# Sheet1.net
KiCad netlist of a schematic drawn in Altium Designer
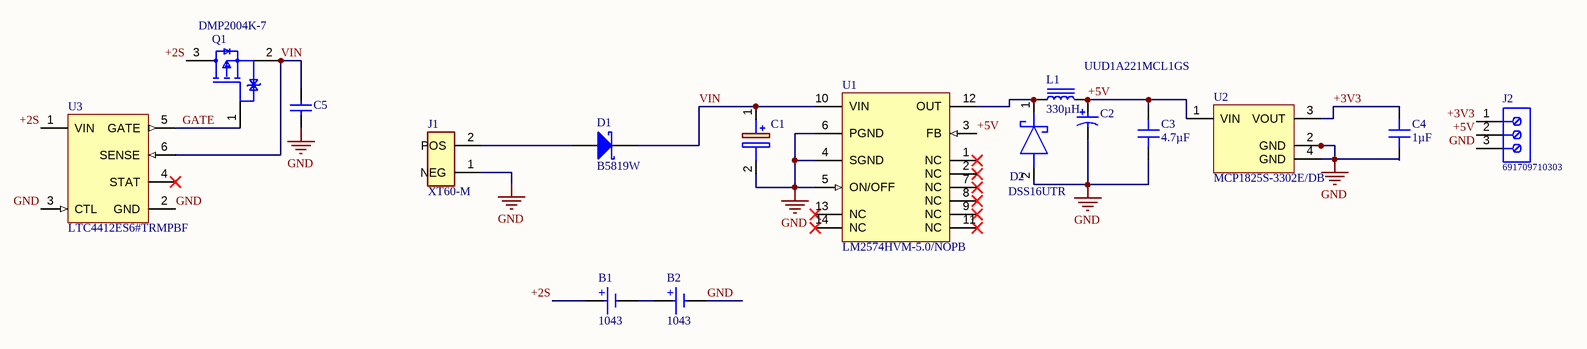
[diagram p0: Sheet1.SchDoc]

(export (version "E")
  (design (tool "Eeschema 10.0.6"))
  (components
    (comp (ref "B1")
      (value "1043")
      (footprint "KEYSTONE 1043")
      (description "BATTERY HOLDER 18650 PC PIN")
      (fields (field (name "MANUFACTURER") "Keystone Electronics"))
      (libsource (lib "Celestial Altium Library - altium_library") (part "Keystone 1043"))
    )
    (comp (ref "B2")
      (value "1043")
      (footprint "KEYSTONE 1043")
      (description "BATTERY HOLDER 18650 PC PIN")
      (fields (field (name "MANUFACTURER") "Keystone Electronics"))
      (libsource (lib "Celestial Altium Library - altium_library") (part "Keystone 1043"))
    )
    (comp (ref "C1")
      (value "EMVH500ADA220MF80G")
      (footprint "SamacSys:CAPAE660X800N")
      (description "Capacitor Polarised")
      (fields (field (name "MOUSER PART NUMBER") "661-MVH50V220M"))
      (libsource (lib "*") (part "EMVH500ADA220MF80G"))
    )
    (comp (ref "C2")
      (value "UUD1A221MCL1GS")
      (footprint "NIC-CAPA2-6.3X7.7_V")
      (fields (field (name "MANUFACTURER") "Nichicon"))
      (libsource (lib "Altium Content Vault") (part "NIC-CAP-P-2"))
    )
    (comp (ref "C3")
      (value "4.7µF")
      (footprint "CAP 1206_3216 - 1.8MM")
      (description "CAP CER 4.7UF 25V X5R 1206")
      (fields
        (field (name "PART NUMBER") "CM316X5R475K25AT")
        (field (name "MANUFACTURER") "Kyocera International Inc. Electronic Components")
      )
      (libsource (lib "Celestial Altium Library - altium_library") (part "Capacitor"))
    )
    (comp (ref "C4")
      (value "1µF")
      (footprint "CAP 1206_3216 - 1.8MM")
      (description "CAP CER 4.7UF 25V X5R 1206")
      (fields
        (field (name "PART NUMBER") "CM316X5R475K25AT")
        (field (name "MANUFACTURER") "Kyocera International Inc. Electronic Components")
      )
      (libsource (lib "Celestial Altium Library - altium_library") (part "Capacitor"))
    )
    (comp (ref "C5")
      (value "C1206C105K5RACTU")
      (footprint "CAPC3216X110X50LL20T25")
      (description "Chip Capacitor, 1 uF, +/- 10%, 50 V, -55 to 125 degC, 1206 (3216 Metric), RoHS, Tape and Reel")
      (fields (field (name "MANUFACTURER") "Kemet") (field (name "TOLERANCE") "10%"))
      (libsource (lib "Altium Content Vault") (part "CAP-NP-2"))
    )
    (comp (ref "D1")
      (value "B5819W")
      (footprint "MCC-SOD123_V")
      (description "Schottky Barrier Rectifier, 40 V, 1 A, -65 to 125 degC, 2-Pin SOD123, RoHS, Tape and Reel")
      (fields (field (name "MANUFACTURER") "Micro Commercial Components"))
      (libsource (lib "Mathewos Samson KSU") (part "DSKY-AK-2"))
    )
    (comp (ref "D2")
      (value "DSS16UTR")
      (footprint "SamacSys:SODFL3618X110N")
      (description "Schottky Diode")
      (libsource (lib "*") (part "DSS16UTR"))
    )
    (comp (ref "J1")
      (value "XT60-M")
      (footprint "AMASS_XT60-M")
      (description "Plug; DC supply; XT60; male; PIN: 2; for cable; soldered; 30A; 500V")
      (fields (field (name "MF") "AMASS"))
      (libsource (lib "XT60-M") (part "XT60-M"))
    )
    (comp (ref "J2")
      (value "691709710303")
      (footprint "691709710303")
      (description "Serie 7097 - 5.00 mm Horizontal Entry SMT with Pressure Clamp WR-TBL, 3 pin")
      (fields (field (name "MANUFACTURER") "Wurth Elektronik") (field (name "PUBLISHER") "WurthElektronik"))
      (libsource (lib "Altium Content Vault") (part "WE-CN-1P-F-TB3"))
    )
    (comp (ref "L1")
      (value "330µH")
      (footprint "BOURNS SRR1280")
      (description "FIXED IND 330UH 1.1A 600MOHM SMD")
      (fields (field (name "PART NUMBER") "SRR1280-331K") (field (name "MANUFACTURER") "Bourns Inc."))
      (libsource (lib "Celestial Altium Library - altium_library") (part "Inductor"))
    )
    (comp (ref "Q1")
      (value "DMP2004K-7")
      (footprint "FP-SOT23-MFG")
      (description "MOSFET P-CH 20V 600MA SOT23-3")
      (fields
        (field (name "OCTOPART") "https://octopart.com/dmp2004k-7-diodes+inc.-7151877")
        (field (name "MANUFACTURER") "Diodes Inc.")
      )
      (libsource (lib "Altium Content Vault") (part "0909edbb8d389a8e80b8543cd1a9d7a"))
    )
    (comp (ref "U1")
      (value "LM2574HVM-5.0/NOPB")
      (footprint "NPA0014B_L")
      (description "SIMPLE SWITCHER® 0.5A Step-Down Voltage Regulator, 14-pin Wide SOIC, Pb-Free")
      (fields (field (name "MANUFACTURER") "Texas Instruments"))
      (libsource (lib "Altium Content Vault") (part "PM-REG-LM2574HVM-12"))
    )
    (comp (ref "U2")
      (value "MCP1825S-3302E/DB")
      (footprint "SOT-223-DB3_N")
      (description "500 mA, Low Voltage, Low Quiescent Current LDO Regulator, 3-Pin SOT-223, Extended Temperature")
      (libsource (lib "Altium Content Vault") (part "PM-LINEREG-MCP1825-IL4"))
    )
    (comp (ref "U3")
      (value "LTC4412ES6#TRMPBF")
      (footprint "LT-S6-6-TSOT-23_N")
      (fields (field (name "MANUFACTURER") "Linear Technology"))
      (libsource (lib "Altium Content Vault") (part "LT-LTC4412_HV-S6-6"))
    )
  )
  (nets
    (net (code "1") (name "/+2S") (class "Default")
      (node (ref "B1") (pin "1") (pinfunction "+_1") (pintype "passive"))
      (node (ref "Q1") (pin "3") (pinfunction "D_3") (pintype "passive"))
      (node (ref "U3") (pin "1") (pinfunction "VIN_1") (pintype "power_in"))
    )
    (net (code "2") (name "/+3V3") (class "Default")
      (node (ref "C4") (pin "2") (pinfunction "2_2") (pintype "passive"))
      (node (ref "J2") (pin "1") (pinfunction "1_1") (pintype "passive"))
      (node (ref "U2") (pin "3") (pinfunction "VOUT_3") (pintype "power_in"))
    )
    (net (code "3") (name "/+5V") (class "Default")
      (node (ref "C2") (pin "1") (pinfunction "1_1") (pintype "passive"))
      (node (ref "C3") (pin "2") (pinfunction "2_2") (pintype "passive"))
      (node (ref "J2") (pin "2") (pinfunction "2_2") (pintype "passive"))
      (node (ref "L1") (pin "2") (pinfunction "2_2") (pintype "passive"))
      (node (ref "U1") (pin "3") (pinfunction "FB_3") (pintype "input"))
      (node (ref "U2") (pin "1") (pinfunction "VIN_1") (pintype "power_in"))
    )
    (net (code "4") (name "/GATE") (class "Default")
      (node (ref "Q1") (pin "1") (pinfunction "G_1") (pintype "passive"))
      (node (ref "U3") (pin "5") (pinfunction "GATE_5") (pintype "output"))
    )
    (net (code "5") (name "/VIN") (class "Default")
      (node (ref "C1") (pin "1") (pinfunction "+_1") (pintype "passive"))
      (node (ref "C5") (pin "2") (pinfunction "2_2") (pintype "passive"))
      (node (ref "D1") (pin "2") (pinfunction "K_2") (pintype "passive"))
      (node (ref "Q1") (pin "2") (pinfunction "S_2") (pintype "passive"))
      (node (ref "U1") (pin "10") (pinfunction "VIN_10") (pintype "power_in"))
      (node (ref "U3") (pin "6") (pinfunction "SENSE_6") (pintype "input"))
    )
    (net (code "6") (name "GND") (class "Default")
      (node (ref "B2") (pin "2") (pinfunction "-_2") (pintype "passive"))
      (node (ref "C1") (pin "2") (pinfunction "-_2") (pintype "passive"))
      (node (ref "C2") (pin "2") (pinfunction "2_2") (pintype "passive"))
      (node (ref "C3") (pin "1") (pinfunction "1_1") (pintype "passive"))
      (node (ref "C4") (pin "1") (pinfunction "1_1") (pintype "passive"))
      (node (ref "C5") (pin "1") (pinfunction "1_1") (pintype "passive"))
      (node (ref "D2") (pin "2") (pinfunction "A_2") (pintype "passive"))
      (node (ref "J1") (pin "1") (pinfunction "NEG_1") (pintype "passive"))
      (node (ref "J2") (pin "3") (pinfunction "3_3") (pintype "passive"))
      (node (ref "U1") (pin "4") (pinfunction "SGND_4") (pintype "power_in"))
      (node (ref "U1") (pin "5") (pinfunction "ON/OFF_5") (pintype "input"))
      (node (ref "U1") (pin "6") (pinfunction "PGND_6") (pintype "power_in"))
      (node (ref "U2") (pin "2") (pinfunction "GND_2") (pintype "power_in"))
      (node (ref "U2") (pin "4") (pinfunction "GND_4") (pintype "power_in"))
      (node (ref "U3") (pin "2") (pinfunction "GND_2") (pintype "power_in"))
      (node (ref "U3") (pin "3") (pinfunction "CTL_3") (pintype "input"))
    )
    (net (code "7") (name "Net-(B1--)") (class "Default")
      (node (ref "B1") (pin "2") (pinfunction "-_2") (pintype "passive"))
      (node (ref "B2") (pin "1") (pinfunction "+_1") (pintype "passive"))
    )
    (net (code "8") (name "Net-(D1-A)") (class "Default")
      (node (ref "D1") (pin "1") (pinfunction "A_1") (pintype "passive"))
      (node (ref "J1") (pin "2") (pinfunction "POS_2") (pintype "passive"))
    )
    (net (code "9") (name "Net-(D2-K)") (class "Default")
      (node (ref "D2") (pin "1") (pinfunction "K_1") (pintype "passive"))
      (node (ref "L1") (pin "1") (pinfunction "1_1") (pintype "passive"))
      (node (ref "U1") (pin "12") (pinfunction "OUT_12") (pintype "power_in"))
    )
    (net (code "10") (name "unconnected-(U1-NC-Pad1)") (class "Default")
      (node (ref "U1") (pin "1") (pinfunction "NC_1") (pintype "passive+no_connect"))
    )
    (net (code "11") (name "unconnected-(U1-NC-Pad2)") (class "Default")
      (node (ref "U1") (pin "2") (pinfunction "NC_2") (pintype "passive+no_connect"))
    )
    (net (code "12") (name "unconnected-(U1-NC-Pad7)") (class "Default")
      (node (ref "U1") (pin "7") (pinfunction "NC_7") (pintype "passive+no_connect"))
    )
    (net (code "13") (name "unconnected-(U1-NC-Pad8)") (class "Default")
      (node (ref "U1") (pin "8") (pinfunction "NC_8") (pintype "passive+no_connect"))
    )
    (net (code "14") (name "unconnected-(U1-NC-Pad9)") (class "Default")
      (node (ref "U1") (pin "9") (pinfunction "NC_9") (pintype "passive+no_connect"))
    )
    (net (code "15") (name "unconnected-(U1-NC-Pad11)") (class "Default")
      (node (ref "U1") (pin "11") (pinfunction "NC_11") (pintype "passive+no_connect"))
    )
    (net (code "16") (name "unconnected-(U1-NC-Pad13)") (class "Default")
      (node (ref "U1") (pin "13") (pinfunction "NC_13") (pintype "passive+no_connect"))
    )
    (net (code "17") (name "unconnected-(U1-NC-Pad14)") (class "Default")
      (node (ref "U1") (pin "14") (pinfunction "NC_14") (pintype "passive+no_connect"))
    )
    (net (code "18") (name "unconnected-(U3-STAT-Pad4)") (class "Default")
      (node (ref "U3") (pin "4") (pinfunction "STAT_4") (pintype "open_collector+no_connect"))
    )
  )
)
